# FTDI.net
KiCad netlist of a schematic drawn in Altium Designer
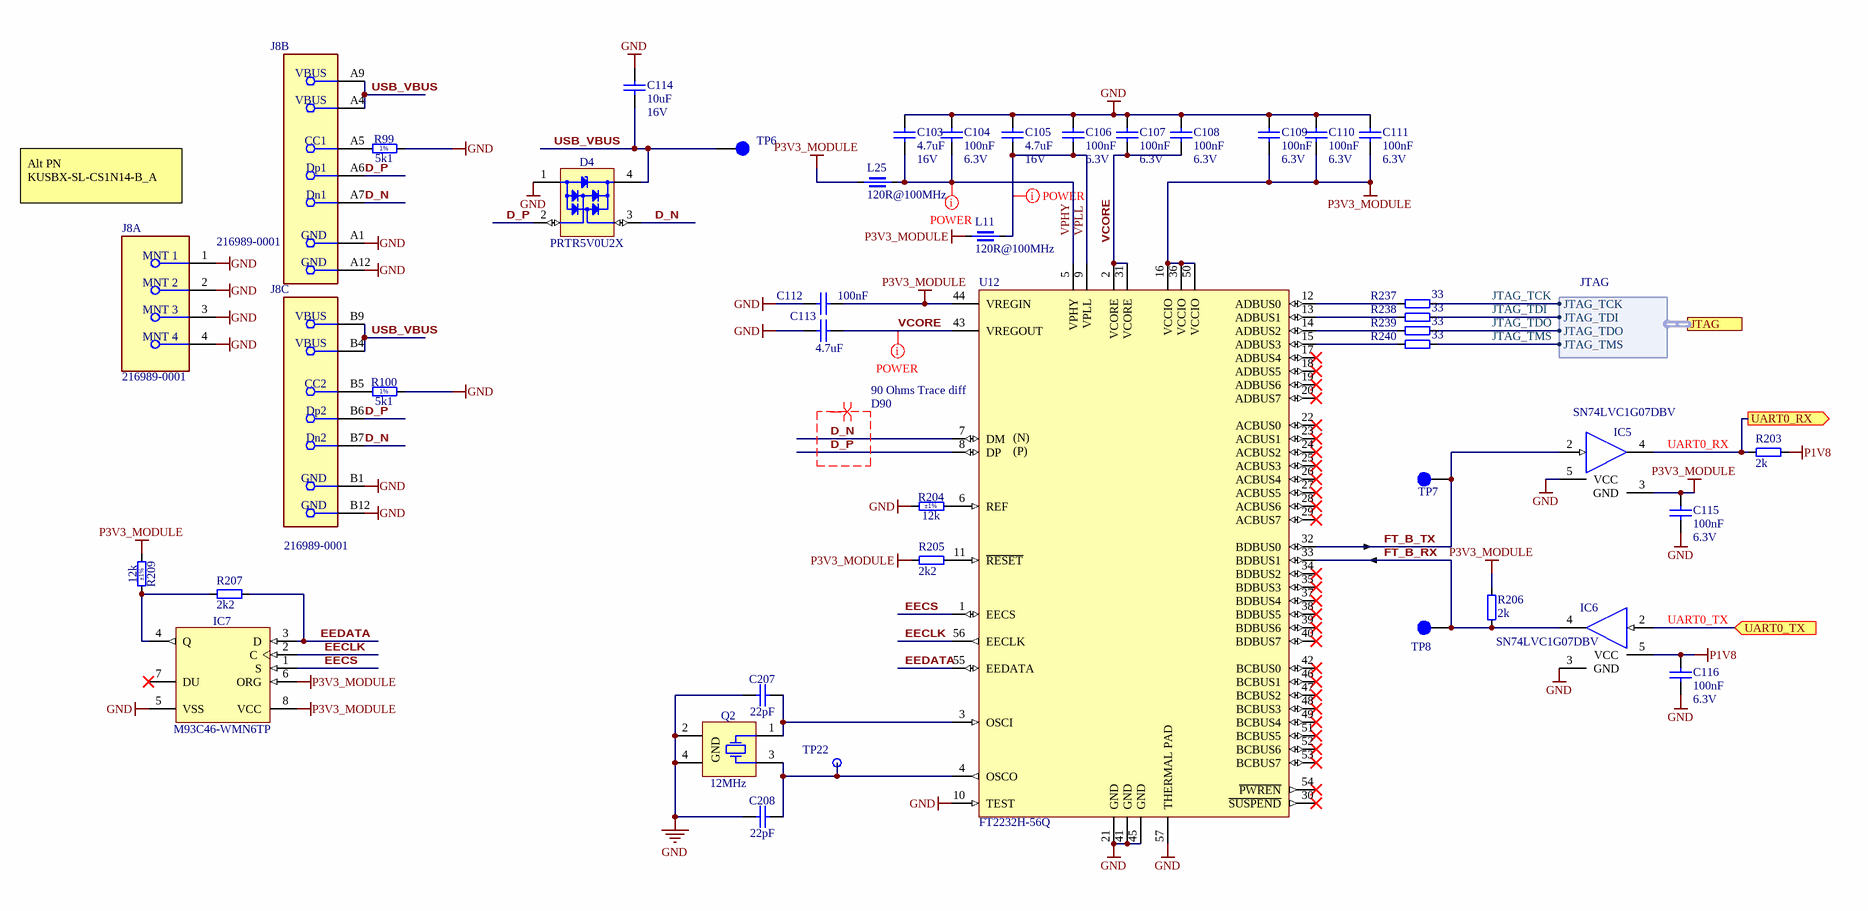
[diagram p0: FTDI.schdoc]

(export (version "E")
  (design (tool "Eeschema 10.0.6"))
  (components
    (comp (ref "C103")
      (value "4.7uF")
      (footprint "CAPC1709X95N")
      (description "Non-polarised capacitor")
      (fields
        (field (name "VOLTAGE") "16V")
        (field (name "TOLERANCE") "±10%")
        (field (name "PART NUMBER") "CC0603_4.7UF_16V_10%_X5R")
        (field (name "AUTHOR") "CERN DEM JLC")
      )
      (libsource (lib "Capacitors") (part "Capacitor - non polarized"))
    )
    (comp (ref "C104")
      (value "100nF")
      (footprint "CAPC0603X33N")
      (description "Non-polarised capacitor")
      (fields
        (field (name "VOLTAGE") "6.3V")
        (field (name "TOLERANCE") "±10%")
        (field (name "PART NUMBER") "CC0201_100NF_6.3V_10%_X7R")
        (field (name "AUTHOR") "CERN DEM BC")
      )
      (libsource (lib "Capacitors") (part "Capacitor - non polarized"))
    )
    (comp (ref "C105")
      (value "4.7uF")
      (footprint "CAPC1709X95N")
      (description "Non-polarised capacitor")
      (fields
        (field (name "VOLTAGE") "16V")
        (field (name "TOLERANCE") "±10%")
        (field (name "PART NUMBER") "CC0603_4.7UF_16V_10%_X5R")
        (field (name "AUTHOR") "CERN DEM JLC")
      )
      (libsource (lib "Capacitors") (part "Capacitor - non polarized"))
    )
    (comp (ref "C106")
      (value "100nF")
      (footprint "CAPC0603X33N")
      (description "Non-polarised capacitor")
      (fields
        (field (name "VOLTAGE") "6.3V")
        (field (name "TOLERANCE") "±10%")
        (field (name "PART NUMBER") "CC0201_100NF_6.3V_10%_X7R")
        (field (name "AUTHOR") "CERN DEM BC")
      )
      (libsource (lib "Capacitors") (part "Capacitor - non polarized"))
    )
    (comp (ref "C107")
      (value "100nF")
      (footprint "CAPC0603X33N")
      (description "Non-polarised capacitor")
      (fields
        (field (name "VOLTAGE") "6.3V")
        (field (name "TOLERANCE") "±10%")
        (field (name "PART NUMBER") "CC0201_100NF_6.3V_10%_X7R")
        (field (name "AUTHOR") "CERN DEM BC")
      )
      (libsource (lib "Capacitors") (part "Capacitor - non polarized"))
    )
    (comp (ref "C108")
      (value "100nF")
      (footprint "CAPC0603X33N")
      (description "Non-polarised capacitor")
      (fields
        (field (name "VOLTAGE") "6.3V")
        (field (name "TOLERANCE") "±10%")
        (field (name "PART NUMBER") "CC0201_100NF_6.3V_10%_X7R")
        (field (name "AUTHOR") "CERN DEM BC")
      )
      (libsource (lib "Capacitors") (part "Capacitor - non polarized"))
    )
    (comp (ref "C109")
      (value "100nF")
      (footprint "CAPC0603X33N")
      (description "Non-polarised capacitor")
      (fields
        (field (name "VOLTAGE") "6.3V")
        (field (name "TOLERANCE") "±10%")
        (field (name "PART NUMBER") "CC0201_100NF_6.3V_10%_X7R")
        (field (name "AUTHOR") "CERN DEM BC")
      )
      (libsource (lib "Capacitors") (part "Capacitor - non polarized"))
    )
    (comp (ref "C110")
      (value "100nF")
      (footprint "CAPC0603X33N")
      (description "Non-polarised capacitor")
      (fields
        (field (name "VOLTAGE") "6.3V")
        (field (name "TOLERANCE") "±10%")
        (field (name "PART NUMBER") "CC0201_100NF_6.3V_10%_X7R")
        (field (name "AUTHOR") "CERN DEM BC")
      )
      (libsource (lib "Capacitors") (part "Capacitor - non polarized"))
    )
    (comp (ref "C111")
      (value "100nF")
      (footprint "CAPC0603X33N")
      (description "Non-polarised capacitor")
      (fields
        (field (name "VOLTAGE") "6.3V")
        (field (name "TOLERANCE") "±10%")
        (field (name "PART NUMBER") "CC0201_100NF_6.3V_10%_X7R")
        (field (name "AUTHOR") "CERN DEM BC")
      )
      (libsource (lib "Capacitors") (part "Capacitor - non polarized"))
    )
    (comp (ref "C112")
      (value "100nF")
      (footprint "CAPC0603X33N")
      (description "Non-polarised capacitor")
      (fields
        (field (name "VOLTAGE") "6.3V")
        (field (name "TOLERANCE") "±10%")
        (field (name "AUTHOR") "CERN DEM BC")
      )
      (libsource (lib "Capacitors") (part "Capacitor - non polarized"))
    )
    (comp (ref "C113")
      (value "4.7uF")
      (footprint "CAPC1709X95N")
      (description "Non-polarised capacitor")
      (fields
        (field (name "VOLTAGE") "16V")
        (field (name "TOLERANCE") "±10%")
        (field (name "AUTHOR") "CERN DEM JLC")
      )
      (libsource (lib "Capacitors") (part "Capacitor - non polarized"))
    )
    (comp (ref "C114")
      (value "10uF")
      (footprint "CAPC1608X80N")
      (description "Non-polarised capacitor")
      (fields
        (field (name "VOLTAGE") "16V")
        (field (name "TOLERANCE") "±20%")
        (field (name "PART NUMBER") "CC0603_10UF_16V_20%_X5R")
        (field (name "AUTHOR") "CERN DEM MR")
      )
      (libsource (lib "Capacitors") (part "Capacitor - non polarized"))
    )
    (comp (ref "C115")
      (value "100nF")
      (footprint "CAPC0603X33N")
      (description "Non-polarised capacitor")
      (fields
        (field (name "VOLTAGE") "6.3V")
        (field (name "TOLERANCE") "±10%")
        (field (name "PART NUMBER") "CC0201_100NF_6.3V_10%_X7R")
        (field (name "AUTHOR") "CERN DEM BC")
      )
      (libsource (lib "Capacitors") (part "Capacitor - non polarized"))
    )
    (comp (ref "C116")
      (value "100nF")
      (footprint "CAPC0603X33N")
      (description "Non-polarised capacitor")
      (fields
        (field (name "VOLTAGE") "6.3V")
        (field (name "TOLERANCE") "±10%")
        (field (name "PART NUMBER") "CC0201_100NF_6.3V_10%_X7R")
        (field (name "AUTHOR") "CERN DEM BC")
      )
      (libsource (lib "Capacitors") (part "Capacitor - non polarized"))
    )
    (comp (ref "C207")
      (value "22pF")
      (footprint "CAPC1005X55N")
      (description "Non-polarised capacitor")
      (fields
        (field (name "PART NUMBER") "CC0402_22PF_50V_5%_C0G")
        (field (name "VOLTAGE") "50V")
        (field (name "AUTHOR") "CERN DEM JLC")
      )
      (libsource (lib "Capacitors") (part "Capacitor - non polarized"))
    )
    (comp (ref "C208")
      (value "22pF")
      (footprint "CAPC1005X55N")
      (description "Non-polarised capacitor")
      (fields
        (field (name "PART NUMBER") "CC0402_22PF_50V_5%_C0G")
        (field (name "VOLTAGE") "50V")
        (field (name "AUTHOR") "CERN DEM JLC")
      )
      (libsource (lib "Capacitors") (part "Capacitor - non polarized"))
    )
    (comp (ref "D4")
      (value "PRTR5V0U2X")
      (footprint "SOT190P230X110-4N")
      (description "Ultra Low Capacitance Double Rail-to-Rail ESD Protection Diode")
      (fields
        (field (name "VOLTAGE") "5.5V")
        (field (name "MANUFACTURER") "NXP SEMICONDUCTORS")
        (field (name "AUTHOR") "CERN DEM JLC")
      )
      (libsource (lib "ICs And Semiconductors") (part "PRTR5V0U2X"))
    )
    (comp (ref "IC5")
      (value "SN74LVC1G07DBV")
      (footprint "SOT95P280X145-5N")
      (description "Single Buffer/Driver With Open-Drain Output")
      (fields (field (name "MANUFACTURER") "TEXAS INSTRUMENTS") (field (name "AUTHOR") "CERN DEM BC"))
      (libsource (lib "ICs And Semiconductors") (part "741G07"))
    )
    (comp (ref "IC6")
      (value "SN74LVC1G07DBV")
      (footprint "SOT95P280X145-5N")
      (description "Single Buffer/Driver With Open-Drain Output")
      (fields (field (name "MANUFACTURER") "TEXAS INSTRUMENTS") (field (name "AUTHOR") "CERN DEM BC"))
      (libsource (lib "ICs And Semiconductors") (part "741G07"))
    )
    (comp (ref "IC7")
      (value "M93C46-WMN6TP")
      (footprint "SOIC127P600X175-8N")
      (description "2.5 to 5.5 V, 1Kb (128x8) Serial Microwire Bus EEPROM")
      (fields (field (name "MANUFACTURER") "ST MICROELECTRONICS") (field (name "AUTHOR") "CERN DEM JLC"))
      (libsource (lib "ICs And Semiconductors") (part "M93C46-WMN6TP"))
    )
    (comp (ref "J8")
      (value "216989-0001")
      (footprint "FP-216989-0001-MFG")
      (description "CONN RCPT USB2.0 TYPE C 24POS RA")
      (libsource (lib "Altium Content Vault") (part "0223f526f2db1734dda50670d79969c"))
    )
    (comp (ref "L11")
      (value "120R@100MHz")
      (footprint "INDC1608X65N")
      (fields
        (field (name "PART NUMBER") "IND0603_MURATA_BLM18SG121TN1D")
        (field (name "POWER") "3A")
        (field (name "TOLERANCE") "±25%")
        (field (name "AUTHOR") "CERN DEM JLC")
      )
      (libsource (lib "Inductors & Transformers") (part "Ferrite Bead"))
    )
    (comp (ref "L25")
      (value "120R@100MHz")
      (footprint "INDC1608X65N")
      (fields
        (field (name "PART NUMBER") "IND0603_MURATA_BLM18SG121TN1D")
        (field (name "POWER") "3A")
        (field (name "TOLERANCE") "±25%")
        (field (name "AUTHOR") "CERN DEM JLC")
      )
      (libsource (lib "Inductors & Transformers") (part "Ferrite Bead"))
    )
    (comp (ref "Q2")
      (value "12MHz")
      (footprint "XTAL_TXC_7M")
      (description "Crystal 4 pins 1=XTAL Control 2=GND3=XTAL 4=GND")
      (fields
        (field (name "PART NUMBER") "XTAL_12MHZ_TXC_7M-12.000MAAJ-T")
        (field (name "MANUFACTURER") "TXC CORPORATION")
        (field (name "AUTHOR") "CERN DEM JLC")
      )
      (libsource (lib "ICs And Semiconductors") (part "Quartz Crystal 1X 2GND 3X 4GND"))
    )
    (comp (ref "R99")
      (value "5k1")
      (footprint "RESC1005X40N")
      (description "Resistor - 1%")
      (fields
        (field (name "PART NUMBER") "R0402_5K1_1%_0.0625W_100PPM")
        (field (name "POWER") "0.0625W")
        (field (name "AUTHOR") "CERN DEM JLC")
      )
      (libsource (lib "Resistors") (part "Resistor - 1%"))
    )
    (comp (ref "R100")
      (value "5k1")
      (footprint "RESC1005X40N")
      (description "Resistor - 1%")
      (fields
        (field (name "PART NUMBER") "R0402_5K1_1%_0.0625W_100PPM")
        (field (name "POWER") "0.0625W")
        (field (name "AUTHOR") "CERN DEM JLC")
      )
      (libsource (lib "Resistors") (part "Resistor - 1%"))
    )
    (comp (ref "R203")
      (value "2k")
      (footprint "RESC1005X40N")
      (description "Resistor - 1%")
      (fields
        (field (name "TOLERANCE") "±1%")
        (field (name "PART NUMBER") "R0402_2K_1%_0.0625W_100PPM")
        (field (name "AUTHOR") "CERN DEM JLC")
      )
      (libsource (lib "Resistors") (part "Resistor - 1%"))
    )
    (comp (ref "R204")
      (value "12k")
      (footprint "RESC1005X40N")
      (description "Resistor - 1%")
      (fields
        (field (name "TOLERANCE") "±1%")
        (field (name "PART NUMBER") "R0402_12K_1%_0.0625W_100PPM")
        (field (name "POWER") "0.0625W")
        (field (name "AUTHOR") "CERN DEM JLC")
      )
      (libsource (lib "Resistors") (part "Resistor - 1%"))
    )
    (comp (ref "R205")
      (value "2k2")
      (footprint "RESC1005X40N")
      (description "Resistor - 1%")
      (fields
        (field (name "TOLERANCE") "±1%")
        (field (name "PART NUMBER") "R0402_2K2_1%_0.0625W_100PPM")
        (field (name "AUTHOR") "CERN DEM JLC")
      )
      (libsource (lib "Resistors") (part "Resistor - 1%"))
    )
    (comp (ref "R206")
      (value "2k")
      (footprint "RESC1005X40N")
      (description "Resistor - 1%")
      (fields
        (field (name "TOLERANCE") "±1%")
        (field (name "PART NUMBER") "R0402_2K_1%_0.0625W_100PPM")
        (field (name "AUTHOR") "CERN DEM JLC")
      )
      (libsource (lib "Resistors") (part "Resistor - 1%"))
    )
    (comp (ref "R207")
      (value "2k2")
      (footprint "RESC1005X40N")
      (description "Resistor - 1%")
      (fields
        (field (name "TOLERANCE") "±1%")
        (field (name "PART NUMBER") "R0402_2K2_1%_0.0625W_100PPM")
        (field (name "AUTHOR") "CERN DEM JLC")
      )
      (libsource (lib "Resistors") (part "Resistor - 1%"))
    )
    (comp (ref "R209")
      (value "12k")
      (footprint "RESC1005X40N")
      (description "Resistor - 1%")
      (fields
        (field (name "TOLERANCE") "±1%")
        (field (name "PART NUMBER") "R0402_12K_1%_0.0625W_100PPM")
        (field (name "POWER") "0.0625W")
        (field (name "AUTHOR") "CERN DEM JLC")
      )
      (libsource (lib "Resistors") (part "Resistor - 1%"))
    )
    (comp (ref "R237")
      (value "33")
      (footprint "RESC1005X40N")
      (description "Resistor - 1%")
      (fields
        (field (name "TOLERANCE") "±1%")
        (field (name "PART NUMBER") "R0402_33R_1%_0.0625W_100PPM")
        (field (name "AUTHOR") "CERN DEM JLC")
      )
      (libsource (lib "Resistors") (part "Resistor - 1%"))
    )
    (comp (ref "R238")
      (value "33")
      (footprint "RESC1005X40N")
      (description "Resistor - 1%")
      (fields
        (field (name "TOLERANCE") "±1%")
        (field (name "PART NUMBER") "R0402_33R_1%_0.0625W_100PPM")
        (field (name "AUTHOR") "CERN DEM JLC")
      )
      (libsource (lib "Resistors") (part "Resistor - 1%"))
    )
    (comp (ref "R239")
      (value "33")
      (footprint "RESC1005X40N")
      (description "Resistor - 1%")
      (fields
        (field (name "TOLERANCE") "±1%")
        (field (name "PART NUMBER") "R0402_33R_1%_0.0625W_100PPM")
        (field (name "AUTHOR") "CERN DEM JLC")
      )
      (libsource (lib "Resistors") (part "Resistor - 1%"))
    )
    (comp (ref "R240")
      (value "33")
      (footprint "RESC1005X40N")
      (description "Resistor - 1%")
      (fields
        (field (name "TOLERANCE") "±1%")
        (field (name "PART NUMBER") "R0402_33R_1%_0.0625W_100PPM")
        (field (name "AUTHOR") "CERN DEM JLC")
      )
      (libsource (lib "Resistors") (part "Resistor - 1%"))
    )
    (comp (ref "TP6") (value "Testpoint 0.8mm") (footprint "TP_0.8mm") (libsource (lib "TE") (part "TP")))
    (comp (ref "TP7") (value "Testpoint 0.8mm") (footprint "TP_0.8mm") (libsource (lib "TE") (part "TP")))
    (comp (ref "TP8") (value "Testpoint 0.8mm") (footprint "TP_0.8mm") (libsource (lib "TE") (part "TP")))
    (comp (ref "TP22")
      (value "Q2")
      (footprint "TPS127")
      (description "Test Point")
      (fields (field (name "PART NUMBER") "SMD_PAD_1.27X1.27MM") (field (name "AUTHOR") "CERN DEM JLC"))
      (libsource (lib "Eletro-mechanical") (part "Test Point"))
    )
    (comp (ref "U12")
      (value "FT2232H-56Q")
      (footprint "QFN50P800X800-57T610X610N")
      (libsource (lib "TE") (part "FT2232H-56Q"))
    )
  )
  (nets
    (net (code "2") (name "/D_N") (class "Default")
      (node (ref "D4") (pin "3") (pinfunction "I/O2_3") (pintype "bidirectional"))
      (node (ref "J8") (pin "A7") (pinfunction "Dn1_A7") (pintype "passive"))
      (node (ref "J8") (pin "B7") (pinfunction "Dn2_B7") (pintype "passive"))
      (node (ref "U12") (pin "7") (pinfunction "DM_7") (pintype "bidirectional"))
    )
    (net (code "3") (name "/D_P") (class "Default")
      (node (ref "D4") (pin "2") (pinfunction "I/O1_2") (pintype "bidirectional"))
      (node (ref "J8") (pin "A6") (pinfunction "Dp1_A6") (pintype "passive"))
      (node (ref "J8") (pin "B6") (pinfunction "Dp2_B6") (pintype "passive"))
      (node (ref "U12") (pin "8") (pinfunction "DP_8") (pintype "bidirectional"))
    )
    (net (code "4") (name "/EECLK") (class "Default")
      (node (ref "IC7") (pin "2") (pinfunction "C_2") (pintype "input"))
      (node (ref "U12") (pin "56") (pinfunction "EECLK_56") (pintype "output"))
    )
    (net (code "5") (name "/EECS") (class "Default")
      (node (ref "IC7") (pin "1") (pinfunction "S_1") (pintype "input"))
      (node (ref "U12") (pin "1") (pinfunction "EECS_1") (pintype "bidirectional"))
    )
    (net (code "6") (name "/EEDATA") (class "Default")
      (node (ref "IC7") (pin "3") (pinfunction "D_3") (pintype "input"))
      (node (ref "R207") (pin "1") (pinfunction "1_1") (pintype "passive"))
      (node (ref "U12") (pin "55") (pinfunction "EEDATA_55") (pintype "bidirectional"))
    )
    (net (code "7") (name "/FT_B_RX") (class "Default")
      (node (ref "IC6") (pin "4") (pinfunction "OUT_4") (pintype "open_collector"))
      (node (ref "R206") (pin "2") (pinfunction "2_2") (pintype "passive"))
      (node (ref "TP8") (pin "1") (pintype "passive"))
      (node (ref "U12") (pin "33") (pinfunction "BDBUS1_33") (pintype "bidirectional"))
    )
    (net (code "8") (name "/FT_B_TX") (class "Default")
      (node (ref "IC5") (pin "2") (pinfunction "IN_2") (pintype "input"))
      (node (ref "TP7") (pin "1") (pintype "passive"))
      (node (ref "U12") (pin "32") (pinfunction "BDBUS0_32") (pintype "bidirectional"))
    )
    (net (code "9") (name "/JTAG_TCK") (class "Default")
      (node (ref "R237") (pin "2") (pinfunction "2_2") (pintype "passive"))
    )
    (net (code "10") (name "/JTAG_TDI") (class "Default")
      (node (ref "R238") (pin "2") (pinfunction "2_2") (pintype "passive"))
    )
    (net (code "11") (name "/JTAG_TDO") (class "Default")
      (node (ref "R239") (pin "2") (pinfunction "2_2") (pintype "passive"))
    )
    (net (code "12") (name "/JTAG_TMS") (class "Default")
      (node (ref "R240") (pin "2") (pinfunction "2_2") (pintype "passive"))
    )
    (net (code "13") (name "/UART0_RX") (class "Default")
      (node (ref "IC5") (pin "4") (pinfunction "OUT_4") (pintype "open_collector"))
      (node (ref "R203") (pin "1") (pinfunction "1_1") (pintype "passive"))
    )
    (net (code "14") (name "/UART0_TX") (class "Default")
      (node (ref "IC6") (pin "2") (pinfunction "IN_2") (pintype "input"))
    )
    (net (code "15") (name "/USB_VBUS") (class "Default")
      (node (ref "C114") (pin "2") (pinfunction "2_2") (pintype "passive"))
      (node (ref "D4") (pin "4") (pinfunction "VCC_4") (pintype "power_in"))
      (node (ref "J8") (pin "A4") (pinfunction "VBUS_A4") (pintype "passive"))
      (node (ref "J8") (pin "A9") (pinfunction "VBUS_A9") (pintype "power_in"))
      (node (ref "J8") (pin "B4") (pinfunction "VBUS_B4") (pintype "passive"))
      (node (ref "J8") (pin "B9") (pinfunction "VBUS_B9") (pintype "passive"))
      (node (ref "TP6") (pin "1") (pintype "passive"))
    )
    (net (code "16") (name "/VCORE") (class "Default")
      (node (ref "C107") (pin "1") (pinfunction "1_1") (pintype "passive"))
      (node (ref "C108") (pin "1") (pinfunction "1_1") (pintype "passive"))
      (node (ref "C113") (pin "2") (pinfunction "2_2") (pintype "passive"))
      (node (ref "U12") (pin "2") (pinfunction "VCORE_2") (pintype "power_in"))
      (node (ref "U12") (pin "31") (pinfunction "VCORE_31") (pintype "power_in"))
      (node (ref "U12") (pin "43") (pinfunction "VREGOUT_43") (pintype "power_in"))
    )
    (net (code "17") (name "/VPHY") (class "Default")
      (node (ref "C103") (pin "1") (pinfunction "1_1") (pintype "passive"))
      (node (ref "C104") (pin "1") (pinfunction "1_1") (pintype "passive"))
      (node (ref "L25") (pin "2") (pinfunction "2_2") (pintype "passive"))
      (node (ref "U12") (pin "5") (pinfunction "VPHY_5") (pintype "power_in"))
    )
    (net (code "18") (name "/VPLL") (class "Default")
      (node (ref "C105") (pin "1") (pinfunction "1_1") (pintype "passive"))
      (node (ref "C106") (pin "1") (pinfunction "1_1") (pintype "passive"))
      (node (ref "L11") (pin "2") (pinfunction "2_2") (pintype "passive"))
      (node (ref "U12") (pin "9") (pinfunction "VPLL_9") (pintype "power_in"))
    )
    (net (code "20") (name "GND") (class "Default")
      (node (ref "C103") (pin "2") (pinfunction "2_2") (pintype "passive"))
      (node (ref "C104") (pin "2") (pinfunction "2_2") (pintype "passive"))
      (node (ref "C105") (pin "2") (pinfunction "2_2") (pintype "passive"))
      (node (ref "C106") (pin "2") (pinfunction "2_2") (pintype "passive"))
      (node (ref "C107") (pin "2") (pinfunction "2_2") (pintype "passive"))
      (node (ref "C108") (pin "2") (pinfunction "2_2") (pintype "passive"))
      (node (ref "C109") (pin "1") (pinfunction "1_1") (pintype "passive"))
      (node (ref "C109") (pin "2") (pinfunction "2_2") (pintype "passive"))
      (node (ref "C110") (pin "1") (pinfunction "1_1") (pintype "passive"))
      (node (ref "C110") (pin "2") (pinfunction "2_2") (pintype "passive"))
      (node (ref "C111") (pin "1") (pinfunction "1_1") (pintype "passive"))
      (node (ref "C111") (pin "2") (pinfunction "2_2") (pintype "passive"))
      (node (ref "C112") (pin "1") (pinfunction "1_1") (pintype "passive"))
      (node (ref "C112") (pin "2") (pinfunction "2_2") (pintype "passive"))
      (node (ref "C113") (pin "1") (pinfunction "1_1") (pintype "passive"))
      (node (ref "C114") (pin "1") (pinfunction "1_1") (pintype "passive"))
      (node (ref "C115") (pin "1") (pinfunction "1_1") (pintype "passive"))
      (node (ref "C115") (pin "2") (pinfunction "2_2") (pintype "passive"))
      (node (ref "C116") (pin "1") (pinfunction "1_1") (pintype "passive"))
      (node (ref "C116") (pin "2") (pinfunction "2_2") (pintype "passive"))
      (node (ref "C207") (pin "1") (pinfunction "1_1") (pintype "passive"))
      (node (ref "C208") (pin "1") (pinfunction "1_1") (pintype "passive"))
      (node (ref "D4") (pin "1") (pinfunction "GND_1") (pintype "power_in"))
      (node (ref "IC5") (pin "3") (pinfunction "GND_3") (pintype "power_in"))
      (node (ref "IC5") (pin "5") (pinfunction "VCC_5") (pintype "power_in"))
      (node (ref "IC6") (pin "3") (pinfunction "GND_3") (pintype "power_in"))
      (node (ref "IC6") (pin "5") (pinfunction "VCC_5") (pintype "power_in"))
      (node (ref "IC7") (pin "5") (pinfunction "VSS_5") (pintype "power_in"))
      (node (ref "IC7") (pin "6") (pinfunction "ORG_6") (pintype "input"))
      (node (ref "IC7") (pin "8") (pinfunction "VCC_8") (pintype "power_in"))
      (node (ref "J8") (pin "1") (pinfunction "MNT_1_1") (pintype "passive"))
      (node (ref "J8") (pin "2") (pinfunction "MNT_2_2") (pintype "passive"))
      (node (ref "J8") (pin "3") (pinfunction "MNT_3_3") (pintype "passive"))
      (node (ref "J8") (pin "4") (pinfunction "MNT_4_4") (pintype "passive"))
      (node (ref "J8") (pin "A1") (pinfunction "GND_A1") (pintype "power_in"))
      (node (ref "J8") (pin "A12") (pinfunction "GND_A12") (pintype "power_in"))
      (node (ref "J8") (pin "B1") (pinfunction "GND_B1") (pintype "power_in"))
      (node (ref "J8") (pin "B12") (pinfunction "GND_B12") (pintype "power_in"))
      (node (ref "L11") (pin "1") (pinfunction "1_1") (pintype "passive"))
      (node (ref "L25") (pin "1") (pinfunction "1_1") (pintype "passive"))
      (node (ref "Q2") (pin "2") (pinfunction "GND_2") (pintype "power_in"))
      (node (ref "Q2") (pin "4") (pinfunction "GND_4") (pintype "power_in"))
      (node (ref "R100") (pin "2") (pinfunction "2_2") (pintype "passive"))
      (node (ref "R203") (pin "2") (pinfunction "2_2") (pintype "passive"))
      (node (ref "R204") (pin "1") (pinfunction "1_1") (pintype "passive"))
      (node (ref "R205") (pin "1") (pinfunction "1_1") (pintype "passive"))
      (node (ref "R206") (pin "1") (pinfunction "1_1") (pintype "passive"))
      (node (ref "R209") (pin "1") (pinfunction "1_1") (pintype "passive"))
      (node (ref "R99") (pin "2") (pinfunction "2_2") (pintype "passive"))
      (node (ref "U12") (pin "10") (pinfunction "TEST_10") (pintype "input"))
      (node (ref "U12") (pin "16") (pinfunction "VCCIO_16") (pintype "power_in"))
      (node (ref "U12") (pin "21") (pinfunction "GND_21") (pintype "power_in"))
      (node (ref "U12") (pin "36") (pinfunction "VCCIO_36") (pintype "power_in"))
      (node (ref "U12") (pin "41") (pinfunction "GND_41") (pintype "power_in"))
      (node (ref "U12") (pin "44") (pinfunction "VREGIN_44") (pintype "power_in"))
      (node (ref "U12") (pin "45") (pinfunction "GND_45") (pintype "power_in"))
      (node (ref "U12") (pin "50") (pinfunction "VCCIO_50") (pintype "power_in"))
      (node (ref "U12") (pin "57") (pinfunction "THERMAL_PAD_57") (pintype "power_in"))
    )
    (net (code "21") (name "Net-(IC7-Q)") (class "Default")
      (node (ref "IC7") (pin "4") (pinfunction "Q_4") (pintype "output"))
      (node (ref "R207") (pin "2") (pinfunction "2_2") (pintype "passive"))
      (node (ref "R209") (pin "2") (pinfunction "2_2") (pintype "passive"))
    )
    (net (code "22") (name "Net-(J8B-CC1)") (class "Default")
      (node (ref "J8") (pin "A5") (pinfunction "CC1_A5") (pintype "passive"))
      (node (ref "R99") (pin "1") (pinfunction "1_1") (pintype "passive"))
    )
    (net (code "23") (name "Net-(J8C-CC2)") (class "Default")
      (node (ref "J8") (pin "B5") (pinfunction "CC2_B5") (pintype "passive"))
      (node (ref "R100") (pin "1") (pinfunction "1_1") (pintype "passive"))
    )
    (net (code "24") (name "Net-(U12-ADBUS0)") (class "Default")
      (node (ref "R237") (pin "1") (pinfunction "1_1") (pintype "passive"))
      (node (ref "U12") (pin "12") (pinfunction "ADBUS0_12") (pintype "bidirectional"))
    )
    (net (code "25") (name "Net-(U12-ADBUS1)") (class "Default")
      (node (ref "R238") (pin "1") (pinfunction "1_1") (pintype "passive"))
      (node (ref "U12") (pin "13") (pinfunction "ADBUS1_13") (pintype "bidirectional"))
    )
    (net (code "26") (name "Net-(U12-ADBUS2)") (class "Default")
      (node (ref "R239") (pin "1") (pinfunction "1_1") (pintype "passive"))
      (node (ref "U12") (pin "14") (pinfunction "ADBUS2_14") (pintype "bidirectional"))
    )
    (net (code "27") (name "Net-(U12-ADBUS3)") (class "Default")
      (node (ref "R240") (pin "1") (pinfunction "1_1") (pintype "passive"))
      (node (ref "U12") (pin "15") (pinfunction "ADBUS3_15") (pintype "bidirectional"))
    )
    (net (code "28") (name "Net-(U12-OSCI)") (class "Default")
      (node (ref "C207") (pin "2") (pinfunction "2_2") (pintype "passive"))
      (node (ref "Q2") (pin "1") (pinfunction "X_1") (pintype "passive"))
      (node (ref "U12") (pin "3") (pinfunction "OSCI_3") (pintype "input"))
    )
    (net (code "29") (name "Net-(U12-OSCO)") (class "Default")
      (node (ref "C208") (pin "2") (pinfunction "2_2") (pintype "passive"))
      (node (ref "Q2") (pin "3") (pinfunction "X_3") (pintype "passive"))
      (node (ref "TP22") (pin "1") (pinfunction "1_1") (pintype "bidirectional"))
      (node (ref "U12") (pin "4") (pinfunction "OSCO_4") (pintype "output"))
    )
    (net (code "30") (name "Net-(U12-REF)") (class "Default")
      (node (ref "R204") (pin "2") (pinfunction "2_2") (pintype "passive"))
      (node (ref "U12") (pin "6") (pinfunction "REF_6") (pintype "input"))
    )
    (net (code "31") (name "Net-(U12-~{RESET})") (class "Default")
      (node (ref "R205") (pin "2") (pinfunction "2_2") (pintype "passive"))
      (node (ref "U12") (pin "11") (pinfunction "~{RESET}_11") (pintype "input"))
    )
    (net (code "32") (name "unconnected-(IC7-DU-Pad7)") (class "Default")
      (node (ref "IC7") (pin "7") (pinfunction "DU_7") (pintype "passive+no_connect"))
    )
    (net (code "33") (name "unconnected-(U12-ACBUS0-Pad22)") (class "Default")
      (node (ref "U12") (pin "22") (pinfunction "ACBUS0_22") (pintype "bidirectional+no_connect"))
    )
    (net (code "34") (name "unconnected-(U12-ACBUS1-Pad23)") (class "Default")
      (node (ref "U12") (pin "23") (pinfunction "ACBUS1_23") (pintype "bidirectional+no_connect"))
    )
    (net (code "35") (name "unconnected-(U12-ACBUS2-Pad24)") (class "Default")
      (node (ref "U12") (pin "24") (pinfunction "ACBUS2_24") (pintype "bidirectional+no_connect"))
    )
    (net (code "36") (name "unconnected-(U12-ACBUS3-Pad25)") (class "Default")
      (node (ref "U12") (pin "25") (pinfunction "ACBUS3_25") (pintype "bidirectional+no_connect"))
    )
    (net (code "37") (name "unconnected-(U12-ACBUS4-Pad26)") (class "Default")
      (node (ref "U12") (pin "26") (pinfunction "ACBUS4_26") (pintype "bidirectional+no_connect"))
    )
    (net (code "38") (name "unconnected-(U12-ACBUS5-Pad27)") (class "Default")
      (node (ref "U12") (pin "27") (pinfunction "ACBUS5_27") (pintype "bidirectional+no_connect"))
    )
    (net (code "39") (name "unconnected-(U12-ACBUS6-Pad28)") (class "Default")
      (node (ref "U12") (pin "28") (pinfunction "ACBUS6_28") (pintype "bidirectional+no_connect"))
    )
    (net (code "40") (name "unconnected-(U12-ACBUS7-Pad29)") (class "Default")
      (node (ref "U12") (pin "29") (pinfunction "ACBUS7_29") (pintype "bidirectional+no_connect"))
    )
    (net (code "41") (name "unconnected-(U12-ADBUS4-Pad17)") (class "Default")
      (node (ref "U12") (pin "17") (pinfunction "ADBUS4_17") (pintype "bidirectional+no_connect"))
    )
    (net (code "42") (name "unconnected-(U12-ADBUS5-Pad18)") (class "Default")
      (node (ref "U12") (pin "18") (pinfunction "ADBUS5_18") (pintype "bidirectional+no_connect"))
    )
    (net (code "43") (name "unconnected-(U12-ADBUS6-Pad19)") (class "Default")
      (node (ref "U12") (pin "19") (pinfunction "ADBUS6_19") (pintype "bidirectional+no_connect"))
    )
    (net (code "44") (name "unconnected-(U12-ADBUS7-Pad20)") (class "Default")
      (node (ref "U12") (pin "20") (pinfunction "ADBUS7_20") (pintype "bidirectional+no_connect"))
    )
    (net (code "45") (name "unconnected-(U12-BCBUS0-Pad42)") (class "Default")
      (node (ref "U12") (pin "42") (pinfunction "BCBUS0_42") (pintype "bidirectional+no_connect"))
    )
    (net (code "46") (name "unconnected-(U12-BCBUS1-Pad46)") (class "Default")
      (node (ref "U12") (pin "46") (pinfunction "BCBUS1_46") (pintype "bidirectional+no_connect"))
    )
    (net (code "47") (name "unconnected-(U12-BCBUS2-Pad47)") (class "Default")
      (node (ref "U12") (pin "47") (pinfunction "BCBUS2_47") (pintype "bidirectional+no_connect"))
    )
    (net (code "48") (name "unconnected-(U12-BCBUS3-Pad48)") (class "Default")
      (node (ref "U12") (pin "48") (pinfunction "BCBUS3_48") (pintype "bidirectional+no_connect"))
    )
    (net (code "49") (name "unconnected-(U12-BCBUS4-Pad49)") (class "Default")
      (node (ref "U12") (pin "49") (pinfunction "BCBUS4_49") (pintype "bidirectional+no_connect"))
    )
    (net (code "50") (name "unconnected-(U12-BCBUS5-Pad51)") (class "Default")
      (node (ref "U12") (pin "51") (pinfunction "BCBUS5_51") (pintype "bidirectional+no_connect"))
    )
    (net (code "51") (name "unconnected-(U12-BCBUS6-Pad52)") (class "Default")
      (node (ref "U12") (pin "52") (pinfunction "BCBUS6_52") (pintype "bidirectional+no_connect"))
    )
    (net (code "52") (name "unconnected-(U12-BCBUS7-Pad53)") (class "Default")
      (node (ref "U12") (pin "53") (pinfunction "BCBUS7_53") (pintype "bidirectional+no_connect"))
    )
    (net (code "53") (name "unconnected-(U12-BDBUS2-Pad34)") (class "Default")
      (node (ref "U12") (pin "34") (pinfunction "BDBUS2_34") (pintype "bidirectional+no_connect"))
    )
    (net (code "54") (name "unconnected-(U12-BDBUS3-Pad35)") (class "Default")
      (node (ref "U12") (pin "35") (pinfunction "BDBUS3_35") (pintype "bidirectional+no_connect"))
    )
    (net (code "55") (name "unconnected-(U12-BDBUS4-Pad37)") (class "Default")
      (node (ref "U12") (pin "37") (pinfunction "BDBUS4_37") (pintype "bidirectional+no_connect"))
    )
    (net (code "56") (name "unconnected-(U12-BDBUS5-Pad38)") (class "Default")
      (node (ref "U12") (pin "38") (pinfunction "BDBUS5_38") (pintype "bidirectional+no_connect"))
    )
    (net (code "57") (name "unconnected-(U12-BDBUS6-Pad39)") (class "Default")
      (node (ref "U12") (pin "39") (pinfunction "BDBUS6_39") (pintype "bidirectional+no_connect"))
    )
    (net (code "58") (name "unconnected-(U12-BDBUS7-Pad40)") (class "Default")
      (node (ref "U12") (pin "40") (pinfunction "BDBUS7_40") (pintype "bidirectional+no_connect"))
    )
    (net (code "59") (name "unconnected-(U12-~{PWREN}-Pad54)") (class "Default")
      (node (ref "U12") (pin "54") (pinfunction "~{PWREN}_54") (pintype "output+no_connect"))
    )
    (net (code "60") (name "unconnected-(U12-~{SUSPEND}-Pad30)") (class "Default")
      (node (ref "U12") (pin "30") (pinfunction "~{SUSPEND}_30") (pintype "output+no_connect"))
    )
  )
)
